# SmartEnergyMeter_schematic.net
KiCad netlist of a schematic drawn in Altium Designer
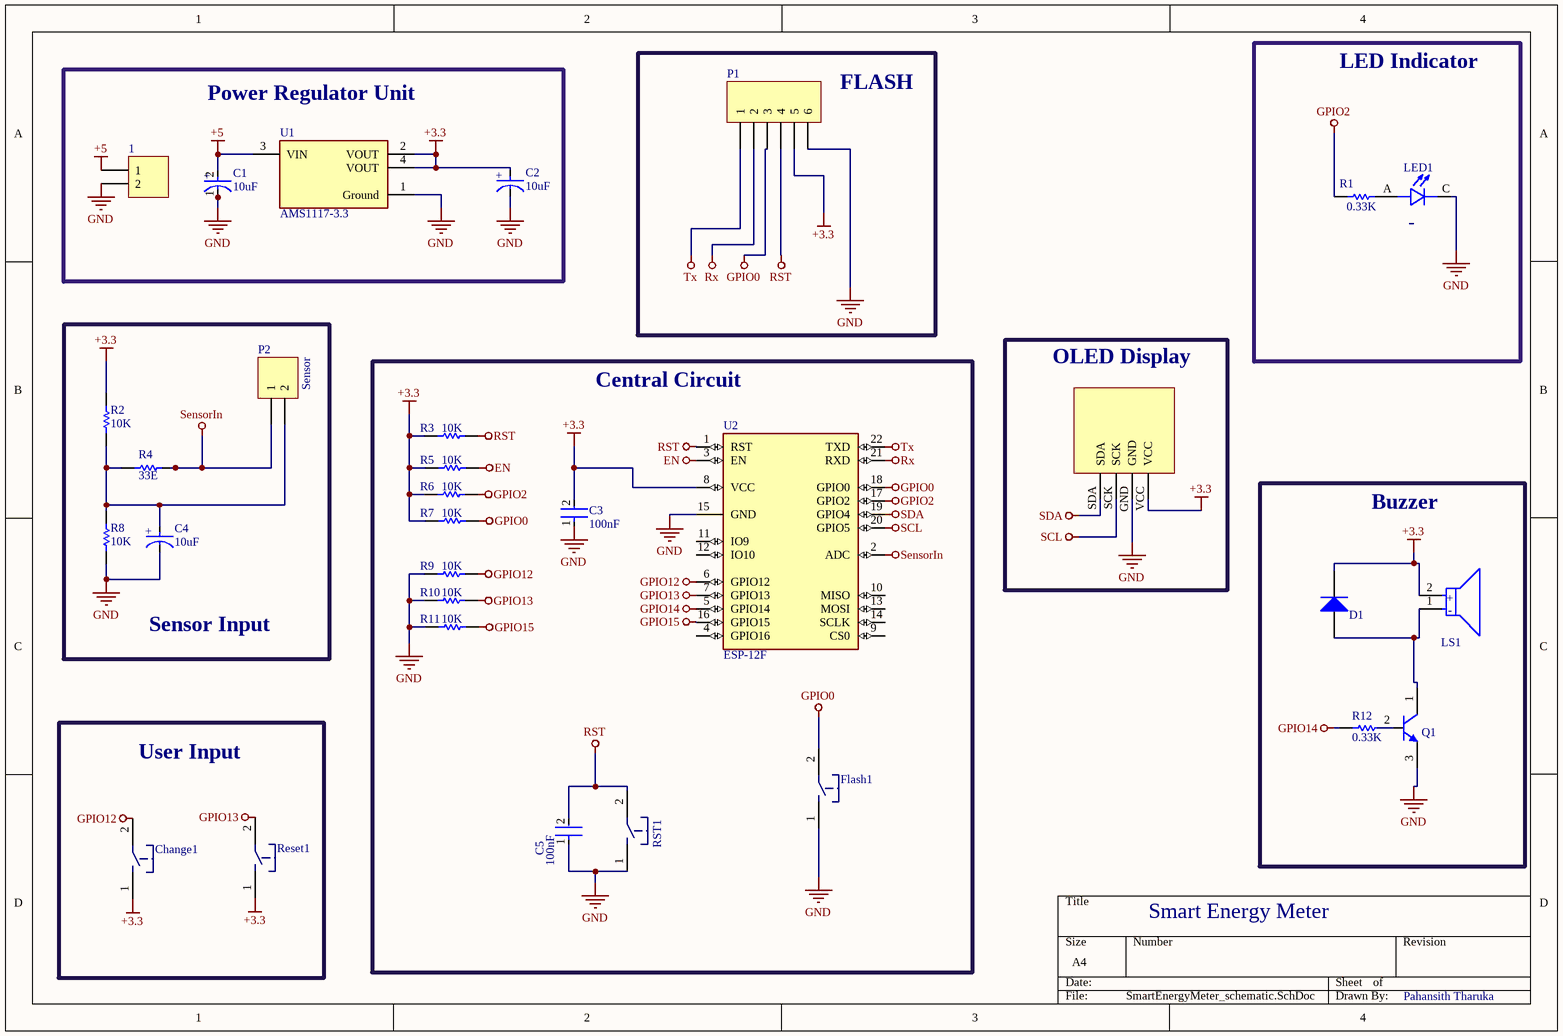
[diagram p0: SmartEnergyMeter_schematic.SchDoc]

(export (version "E")
  (design (tool "Eeschema 10.0.6"))
  (components
    (comp (ref "1")
      (value "Header 3")
      (footprint "HDR1X2")
      (description "Header, 2-Pin")
      (fields (field (name "PUBLISHER") "Altium Limited"))
      (libsource (lib "Miscellaneous Connectors") (part "Header 2"))
    )
    (comp (ref "C1")
      (value "10uF")
      (footprint "FP-RAD-TH-D_5_0_5-L_11_1-MFG")
      (description "Aluminum Electrolytic Capacitors (Radial Lead Type) AEC-Q200 Qualified 10uF ±20% 50V")
      (fields (field (name "TOLERANCE") "20%"))
      (libsource (lib "Altium Content Vault") (part "a00bbbee19879c290e62620ae7e47b1"))
    )
    (comp (ref "C2")
      (value "10uF")
      (footprint "FP-RAD-TH-D_5_0_5-L_11_1-MFG")
      (description "Aluminum Electrolytic Capacitors (Radial Lead Type) AEC-Q200 Qualified 10uF ±20% 50V")
      (fields (field (name "TOLERANCE") "20%"))
      (libsource (lib "") (part "a00bbbee19879c290e62620ae7e47b1_1"))
    )
    (comp (ref "C3")
      (value "100nF")
      (footprint "FP-C322C104K5R5TA-MFG")
      (description "CAP CER 0.1UF 50V X7R RADIAL")
      (fields (field (name "TOLERANCE") "10%") (field (name "VOLTAGE") "50V"))
      (libsource (lib "Altium Content Vault") (part "b4654b650e69147ec39a6b967a45e02"))
    )
    (comp (ref "C4")
      (value "10uF")
      (footprint "FP-RAD-TH-D_5_0_5-L_11_1-MFG")
      (description "Aluminum Electrolytic Capacitors (Radial Lead Type) AEC-Q200 Qualified 10uF ±20% 50V")
      (fields (field (name "TOLERANCE") "20%"))
      (libsource (lib "") (part "a00bbbee19879c290e62620ae7e47b1_1"))
    )
    (comp (ref "C5")
      (value "100nF")
      (footprint "FP-C322C104K5R5TA-MFG")
      (description "CAP CER 0.1UF 50V X7R RADIAL")
      (fields (field (name "TOLERANCE") "10%") (field (name "VOLTAGE") "50V"))
      (libsource (lib "Altium Content Vault") (part "b4654b650e69147ec39a6b967a45e02"))
    )
    (comp (ref "Change1")
      (value "Tac switch")
      (footprint "MY_TACTILE-PTH")
      (description "small tac switch")
      (fields (field (name "ASID PART NUMBER") "Tac switch-AS"))
      (libsource (lib "Mylib+Rev+4") (part "Tac switch"))
    )
    (comp (ref "D1")
      (value "1N4007")
      (footprint "My_DO41")
      (description "1 Amp Diode")
      (fields (field (name "ASID PART NUMBER") "1n4007-AS"))
      (libsource (lib "Mylib+Rev+4") (part "1N4007"))
    )
    (comp (ref "Flash1")
      (value "Tac switch")
      (footprint "MY_TACTILE-PTH")
      (description "small tac switch")
      (fields (field (name "ASID PART NUMBER") "Tac switch-AS"))
      (libsource (lib "Mylib+Rev+4") (part "Tac switch"))
    )
    (comp (ref "LED1")
      (value "L08R5000Q1")
      (footprint "LEDRD254W57D500H1070")
      (fields (field (name "MF") "LED Technology"))
      (libsource (lib "L08R5000Q1") (part "L08R5000Q1"))
    )
    (comp (ref "LS1")
      (value "SDC1610M5-01")
      (footprint "FP-SDC1610M5-01-MFG")
      (description "AUDIO MAGNETIC INDICATOR 4-8V TH")
      (libsource (lib "Altium Content Vault") (part "f7ec632b6fea80cbef86dc3340f200c"))
    )
    (comp (ref "OLED Display1")
      (value "OLED Display")
      (footprint "PCBComponent_1")
      (libsource (lib "oled") (part "OLED Display"))
    )
    (comp (ref "P1")
      (value "Header 6")
      (footprint "My_1X06")
      (description "Header, 6-Pin")
      (fields (field (name "ASID PART NUMBER") "Header 6-AS"))
      (libsource (lib "Mylib+Rev+4") (part "Header 6"))
    )
    (comp (ref "P2")
      (value "Sensor")
      (footprint "HDR1X2")
      (description "Header, 2-Pin")
      (fields (field (name "PUBLISHER") "Altium Limited"))
      (libsource (lib "") (part "Header 2_1"))
    )
    (comp (ref "Q1")
      (value "BC546BRL1G")
      (footprint "ONSC-TO-92-3-29-11_AM_BL")
      (description "Amplifier Transistor, NPN Silicon, 3-Pin TO-92, Pb-Free, Tape and Reel")
      (fields (field (name "MANUFACTURER") "On Semiconductor"))
      (libsource (lib "Altium Content Vault") (part "ONSC-NPN-C1B2E3-3"))
    )
    (comp (ref "R1")
      (value "0.33K")
      (footprint "OMTE-RES7X2.5-2")
      (fields
        (field (name "TOLERANCE") "±5%")
        (field (name "PARTNUMBER") "OD103JE")
        (field (name "MANUFACTURER") "Ohmite")
      )
      (libsource (lib "Altium Content Vault") (part "RES-2"))
    )
    (comp (ref "R2")
      (value "10K")
      (footprint "OMTE-RES7X2.5-2")
      (fields
        (field (name "TOLERANCE") "±5%")
        (field (name "PARTNUMBER") "OD103JE")
        (field (name "MANUFACTURER") "Ohmite")
      )
      (libsource (lib "Altium Content Vault") (part "RES-2"))
    )
    (comp (ref "R3")
      (value "10K")
      (footprint "OMTE-RES7X2.5-2")
      (fields
        (field (name "TOLERANCE") "±5%")
        (field (name "PARTNUMBER") "OD103JE")
        (field (name "MANUFACTURER") "Ohmite")
      )
      (libsource (lib "Altium Content Vault") (part "RES-2"))
    )
    (comp (ref "R4")
      (value "33E")
      (footprint "OMTE-RES7X2.5-2")
      (fields
        (field (name "TOLERANCE") "±5%")
        (field (name "PARTNUMBER") "OD103JE")
        (field (name "MANUFACTURER") "Ohmite")
      )
      (libsource (lib "Altium Content Vault") (part "RES-2"))
    )
    (comp (ref "R5")
      (value "10K")
      (footprint "OMTE-RES7X2.5-2")
      (fields
        (field (name "TOLERANCE") "±5%")
        (field (name "PARTNUMBER") "OD103JE")
        (field (name "MANUFACTURER") "Ohmite")
      )
      (libsource (lib "Altium Content Vault") (part "RES-2"))
    )
    (comp (ref "R6")
      (value "10K")
      (footprint "OMTE-RES7X2.5-2")
      (fields
        (field (name "TOLERANCE") "±5%")
        (field (name "PARTNUMBER") "OD103JE")
        (field (name "MANUFACTURER") "Ohmite")
      )
      (libsource (lib "Altium Content Vault") (part "RES-2"))
    )
    (comp (ref "R7")
      (value "10K")
      (footprint "OMTE-RES7X2.5-2")
      (fields
        (field (name "TOLERANCE") "±5%")
        (field (name "PARTNUMBER") "OD103JE")
        (field (name "MANUFACTURER") "Ohmite")
      )
      (libsource (lib "Altium Content Vault") (part "RES-2"))
    )
    (comp (ref "R8")
      (value "10K")
      (footprint "OMTE-RES7X2.5-2")
      (fields
        (field (name "TOLERANCE") "±5%")
        (field (name "PARTNUMBER") "OD103JE")
        (field (name "MANUFACTURER") "Ohmite")
      )
      (libsource (lib "Altium Content Vault") (part "RES-2"))
    )
    (comp (ref "R9")
      (value "10K")
      (footprint "OMTE-RES7X2.5-2")
      (fields
        (field (name "TOLERANCE") "±5%")
        (field (name "PARTNUMBER") "OD103JE")
        (field (name "MANUFACTURER") "Ohmite")
      )
      (libsource (lib "Altium Content Vault") (part "RES-2"))
    )
    (comp (ref "R10")
      (value "10K")
      (footprint "OMTE-RES7X2.5-2")
      (fields
        (field (name "TOLERANCE") "±5%")
        (field (name "PARTNUMBER") "OD103JE")
        (field (name "MANUFACTURER") "Ohmite")
      )
      (libsource (lib "Altium Content Vault") (part "RES-2"))
    )
    (comp (ref "R11")
      (value "10K")
      (footprint "OMTE-RES7X2.5-2")
      (fields
        (field (name "TOLERANCE") "±5%")
        (field (name "PARTNUMBER") "OD103JE")
        (field (name "MANUFACTURER") "Ohmite")
      )
      (libsource (lib "Altium Content Vault") (part "RES-2"))
    )
    (comp (ref "R12")
      (value "0.33K")
      (footprint "OMTE-RES7X2.5-2")
      (fields
        (field (name "TOLERANCE") "±5%")
        (field (name "PARTNUMBER") "OD103JE")
        (field (name "MANUFACTURER") "Ohmite")
      )
      (libsource (lib "Altium Content Vault") (part "RES-2"))
    )
    (comp (ref "Reset1")
      (value "Tac switch")
      (footprint "MY_TACTILE-PTH")
      (description "small tac switch")
      (fields (field (name "ASID PART NUMBER") "Tac switch-AS"))
      (libsource (lib "Mylib+Rev+4") (part "Tac switch"))
    )
    (comp (ref "RST1")
      (value "Tac switch")
      (footprint "MY_TACTILE-PTH")
      (description "small tac switch")
      (fields (field (name "ASID PART NUMBER") "Tac switch-AS"))
      (libsource (lib "Mylib+Rev+4") (part "Tac switch"))
    )
    (comp (ref "U1")
      (value "AMS1117-3.3")
      (footprint "FP-AMS1117-IPC_C")
      (description "LDO Voltage Regulators 1A, 3.3V")
      (fields
        (field (name "OCTOPART") "https://octopart.com/ams1117-3.3-advanced+monolithic+systems-25899300")
        (field (name "MANUFACTURER") "Advanced Monolithic Systems")
      )
      (libsource (lib "Altium Content Vault") (part "8bdbb5f8e77002000e30dd2845d0354"))
    )
    (comp (ref "U2")
      (value "ESP-12F")
      (footprint "ESP-12F")
      (description "WiFi Module")
      (fields (field (name "MF") "AI-Thinker"))
      (libsource (lib "ESP-12F") (part "ESP-12F"))
    )
  )
  (nets
    (net (code "1") (name "+3.3") (class "Default")
      (node (ref "C2") (pin "2") (pinfunction "A_2") (pintype "passive"))
      (node (ref "C3") (pin "2") (pinfunction "2_2") (pintype "passive"))
      (node (ref "Change1") (pin "1") (pinfunction "1_1") (pintype "passive"))
      (node (ref "D1") (pin "K") (pinfunction "K_K") (pintype "passive"))
      (node (ref "LS1") (pin "2") (pinfunction "A_2") (pintype "passive"))
      (node (ref "OLED Display1") (pin "VCC") (pinfunction "VCC_VCC") (pintype "passive"))
      (node (ref "P1") (pin "5") (pinfunction "5_5") (pintype "passive"))
      (node (ref "R2") (pin "2") (pinfunction "2_2") (pintype "passive"))
      (node (ref "R3") (pin "1") (pinfunction "1_1") (pintype "passive"))
      (node (ref "R5") (pin "1") (pinfunction "1_1") (pintype "passive"))
      (node (ref "R6") (pin "2") (pinfunction "2_2") (pintype "passive"))
      (node (ref "R7") (pin "1") (pinfunction "1_1") (pintype "passive"))
      (node (ref "Reset1") (pin "1") (pinfunction "1_1") (pintype "passive"))
      (node (ref "U1") (pin "2") (pinfunction "VOUT_2") (pintype "passive"))
      (node (ref "U1") (pin "4") (pinfunction "VOUT_4") (pintype "passive"))
      (node (ref "U2") (pin "8") (pinfunction "VCC_8") (pintype "bidirectional"))
    )
    (net (code "2") (name "+5") (class "Default")
      (node (ref "1") (pin "1") (pinfunction "1_1") (pintype "passive"))
      (node (ref "C1") (pin "2") (pinfunction "A_2") (pintype "passive"))
      (node (ref "U1") (pin "3") (pinfunction "VIN_3") (pintype "power_in"))
    )
    (net (code "3") (name "EN") (class "Default")
      (node (ref "R5") (pin "2") (pinfunction "2_2") (pintype "passive"))
      (node (ref "U2") (pin "3") (pinfunction "EN_3") (pintype "bidirectional"))
    )
    (net (code "4") (name "GND") (class "Default")
      (node (ref "1") (pin "2") (pinfunction "2_2") (pintype "passive"))
      (node (ref "C1") (pin "1") (pinfunction "C_1") (pintype "passive"))
      (node (ref "C2") (pin "1") (pinfunction "C_1") (pintype "passive"))
      (node (ref "C3") (pin "1") (pinfunction "1_1") (pintype "passive"))
      (node (ref "C4") (pin "1") (pinfunction "C_1") (pintype "passive"))
      (node (ref "C5") (pin "1") (pinfunction "1_1") (pintype "passive"))
      (node (ref "Flash1") (pin "1") (pinfunction "1_1") (pintype "passive"))
      (node (ref "LED1") (pin "C") (pinfunction "C_C") (pintype "passive"))
      (node (ref "OLED Display1") (pin "GND") (pinfunction "GND_GND") (pintype "passive"))
      (node (ref "P1") (pin "6") (pinfunction "6_6") (pintype "passive"))
      (node (ref "Q1") (pin "3") (pinfunction "E_3") (pintype "passive"))
      (node (ref "R10") (pin "2") (pinfunction "2_2") (pintype "passive"))
      (node (ref "R11") (pin "2") (pinfunction "2_2") (pintype "passive"))
      (node (ref "R8") (pin "1") (pinfunction "1_1") (pintype "passive"))
      (node (ref "R9") (pin "2") (pinfunction "2_2") (pintype "passive"))
      (node (ref "RST1") (pin "1") (pinfunction "1_1") (pintype "passive"))
      (node (ref "U1") (pin "1") (pinfunction "Ground_1") (pintype "power_in"))
      (node (ref "U2") (pin "15") (pinfunction "GND_15") (pintype "power_in"))
    )
    (net (code "5") (name "GPIO0") (class "Default")
      (node (ref "Flash1") (pin "2") (pinfunction "2_2") (pintype "passive"))
      (node (ref "P1") (pin "3") (pinfunction "3_3") (pintype "passive"))
      (node (ref "R7") (pin "2") (pinfunction "2_2") (pintype "passive"))
      (node (ref "U2") (pin "18") (pinfunction "GPIO0_18") (pintype "bidirectional"))
    )
    (net (code "6") (name "GPIO2") (class "Default")
      (node (ref "R1") (pin "1") (pinfunction "1_1") (pintype "passive"))
      (node (ref "R6") (pin "1") (pinfunction "1_1") (pintype "passive"))
      (node (ref "U2") (pin "17") (pinfunction "GPIO2_17") (pintype "bidirectional"))
    )
    (net (code "7") (name "GPIO12") (class "Default")
      (node (ref "Change1") (pin "2") (pinfunction "2_2") (pintype "passive"))
      (node (ref "R9") (pin "1") (pinfunction "1_1") (pintype "passive"))
      (node (ref "U2") (pin "6") (pinfunction "GPIO12_6") (pintype "bidirectional"))
    )
    (net (code "8") (name "GPIO13") (class "Default")
      (node (ref "R10") (pin "1") (pinfunction "1_1") (pintype "passive"))
      (node (ref "Reset1") (pin "2") (pinfunction "2_2") (pintype "passive"))
      (node (ref "U2") (pin "7") (pinfunction "GPIO13_7") (pintype "bidirectional"))
    )
    (net (code "9") (name "GPIO14") (class "Default")
      (node (ref "R12") (pin "1") (pinfunction "1_1") (pintype "passive"))
      (node (ref "U2") (pin "5") (pinfunction "GPIO14_5") (pintype "bidirectional"))
    )
    (net (code "10") (name "GPIO15") (class "Default")
      (node (ref "R11") (pin "1") (pinfunction "1_1") (pintype "passive"))
      (node (ref "U2") (pin "16") (pinfunction "GPIO15_16") (pintype "bidirectional"))
    )
    (net (code "11") (name "Net-(C4-A)") (class "Default")
      (node (ref "C4") (pin "2") (pinfunction "A_2") (pintype "passive"))
      (node (ref "P2") (pin "2") (pinfunction "2_2") (pintype "passive"))
      (node (ref "R2") (pin "1") (pinfunction "1_1") (pintype "passive"))
      (node (ref "R4") (pin "2") (pinfunction "2_2") (pintype "passive"))
      (node (ref "R8") (pin "2") (pinfunction "2_2") (pintype "passive"))
    )
    (net (code "12") (name "Net-(LS1-C)") (class "Default")
      (node (ref "D1") (pin "A") (pinfunction "A_A") (pintype "passive"))
      (node (ref "LS1") (pin "1") (pinfunction "C_1") (pintype "passive"))
      (node (ref "Q1") (pin "1") (pinfunction "C_1") (pintype "passive"))
    )
    (net (code "13") (name "Net-(Q1-B)") (class "Default")
      (node (ref "Q1") (pin "2") (pinfunction "B_2") (pintype "passive"))
      (node (ref "R12") (pin "2") (pinfunction "2_2") (pintype "passive"))
    )
    (net (code "14") (name "RST") (class "Default")
      (node (ref "C5") (pin "2") (pinfunction "2_2") (pintype "passive"))
      (node (ref "P1") (pin "4") (pinfunction "4_4") (pintype "passive"))
      (node (ref "R3") (pin "2") (pinfunction "2_2") (pintype "passive"))
      (node (ref "RST1") (pin "2") (pinfunction "2_2") (pintype "passive"))
      (node (ref "U2") (pin "1") (pinfunction "RST_1") (pintype "bidirectional"))
    )
    (net (code "15") (name "Rx") (class "Default")
      (node (ref "P1") (pin "2") (pinfunction "2_2") (pintype "passive"))
      (node (ref "U2") (pin "21") (pinfunction "RXD_21") (pintype "bidirectional"))
    )
    (net (code "16") (name "SCL") (class "Default")
      (node (ref "OLED Display1") (pin "SCK") (pinfunction "SCK_SCK") (pintype "passive"))
      (node (ref "U2") (pin "20") (pinfunction "GPIO5_20") (pintype "bidirectional"))
    )
    (net (code "17") (name "SDA") (class "Default")
      (node (ref "OLED Display1") (pin "SDA") (pinfunction "SDA_SDA") (pintype "passive"))
      (node (ref "U2") (pin "19") (pinfunction "GPIO4_19") (pintype "bidirectional"))
    )
    (net (code "18") (name "SensorIn") (class "Default")
      (node (ref "P2") (pin "1") (pinfunction "1_1") (pintype "passive"))
      (node (ref "R4") (pin "1") (pinfunction "1_1") (pintype "passive"))
      (node (ref "U2") (pin "2") (pinfunction "ADC_2") (pintype "bidirectional"))
    )
    (net (code "19") (name "Tx") (class "Default")
      (node (ref "P1") (pin "1") (pinfunction "1_1") (pintype "passive"))
      (node (ref "U2") (pin "22") (pinfunction "TXD_22") (pintype "bidirectional"))
    )
    (net (code "20") (name "unconnected-(LED1-PadA)") (class "Default")
      (node (ref "LED1") (pin "A") (pinfunction "A_A") (pintype "passive"))
    )
    (net (code "21") (name "unconnected-(R1-Pad2)") (class "Default")
      (node (ref "R1") (pin "2") (pinfunction "2_2") (pintype "passive"))
    )
    (net (code "22") (name "unconnected-(U2-CS0-Pad9)") (class "Default")
      (node (ref "U2") (pin "9") (pinfunction "CS0_9") (pintype "bidirectional"))
    )
    (net (code "23") (name "unconnected-(U2-GPIO16-Pad4)") (class "Default")
      (node (ref "U2") (pin "4") (pinfunction "GPIO16_4") (pintype "bidirectional"))
    )
    (net (code "24") (name "unconnected-(U2-IO9-Pad11)") (class "Default")
      (node (ref "U2") (pin "11") (pinfunction "IO9_11") (pintype "bidirectional"))
    )
    (net (code "25") (name "unconnected-(U2-IO10-Pad12)") (class "Default")
      (node (ref "U2") (pin "12") (pinfunction "IO10_12") (pintype "bidirectional"))
    )
    (net (code "26") (name "unconnected-(U2-MISO-Pad10)") (class "Default")
      (node (ref "U2") (pin "10") (pinfunction "MISO_10") (pintype "bidirectional"))
    )
    (net (code "27") (name "unconnected-(U2-MOSI-Pad13)") (class "Default")
      (node (ref "U2") (pin "13") (pinfunction "MOSI_13") (pintype "bidirectional"))
    )
    (net (code "28") (name "unconnected-(U2-SCLK-Pad14)") (class "Default")
      (node (ref "U2") (pin "14") (pinfunction "SCLK_14") (pintype "bidirectional"))
    )
  )
)
